# 19_SOLENOID_HB_1.net
KiCad netlist of a schematic drawn in Altium Designer
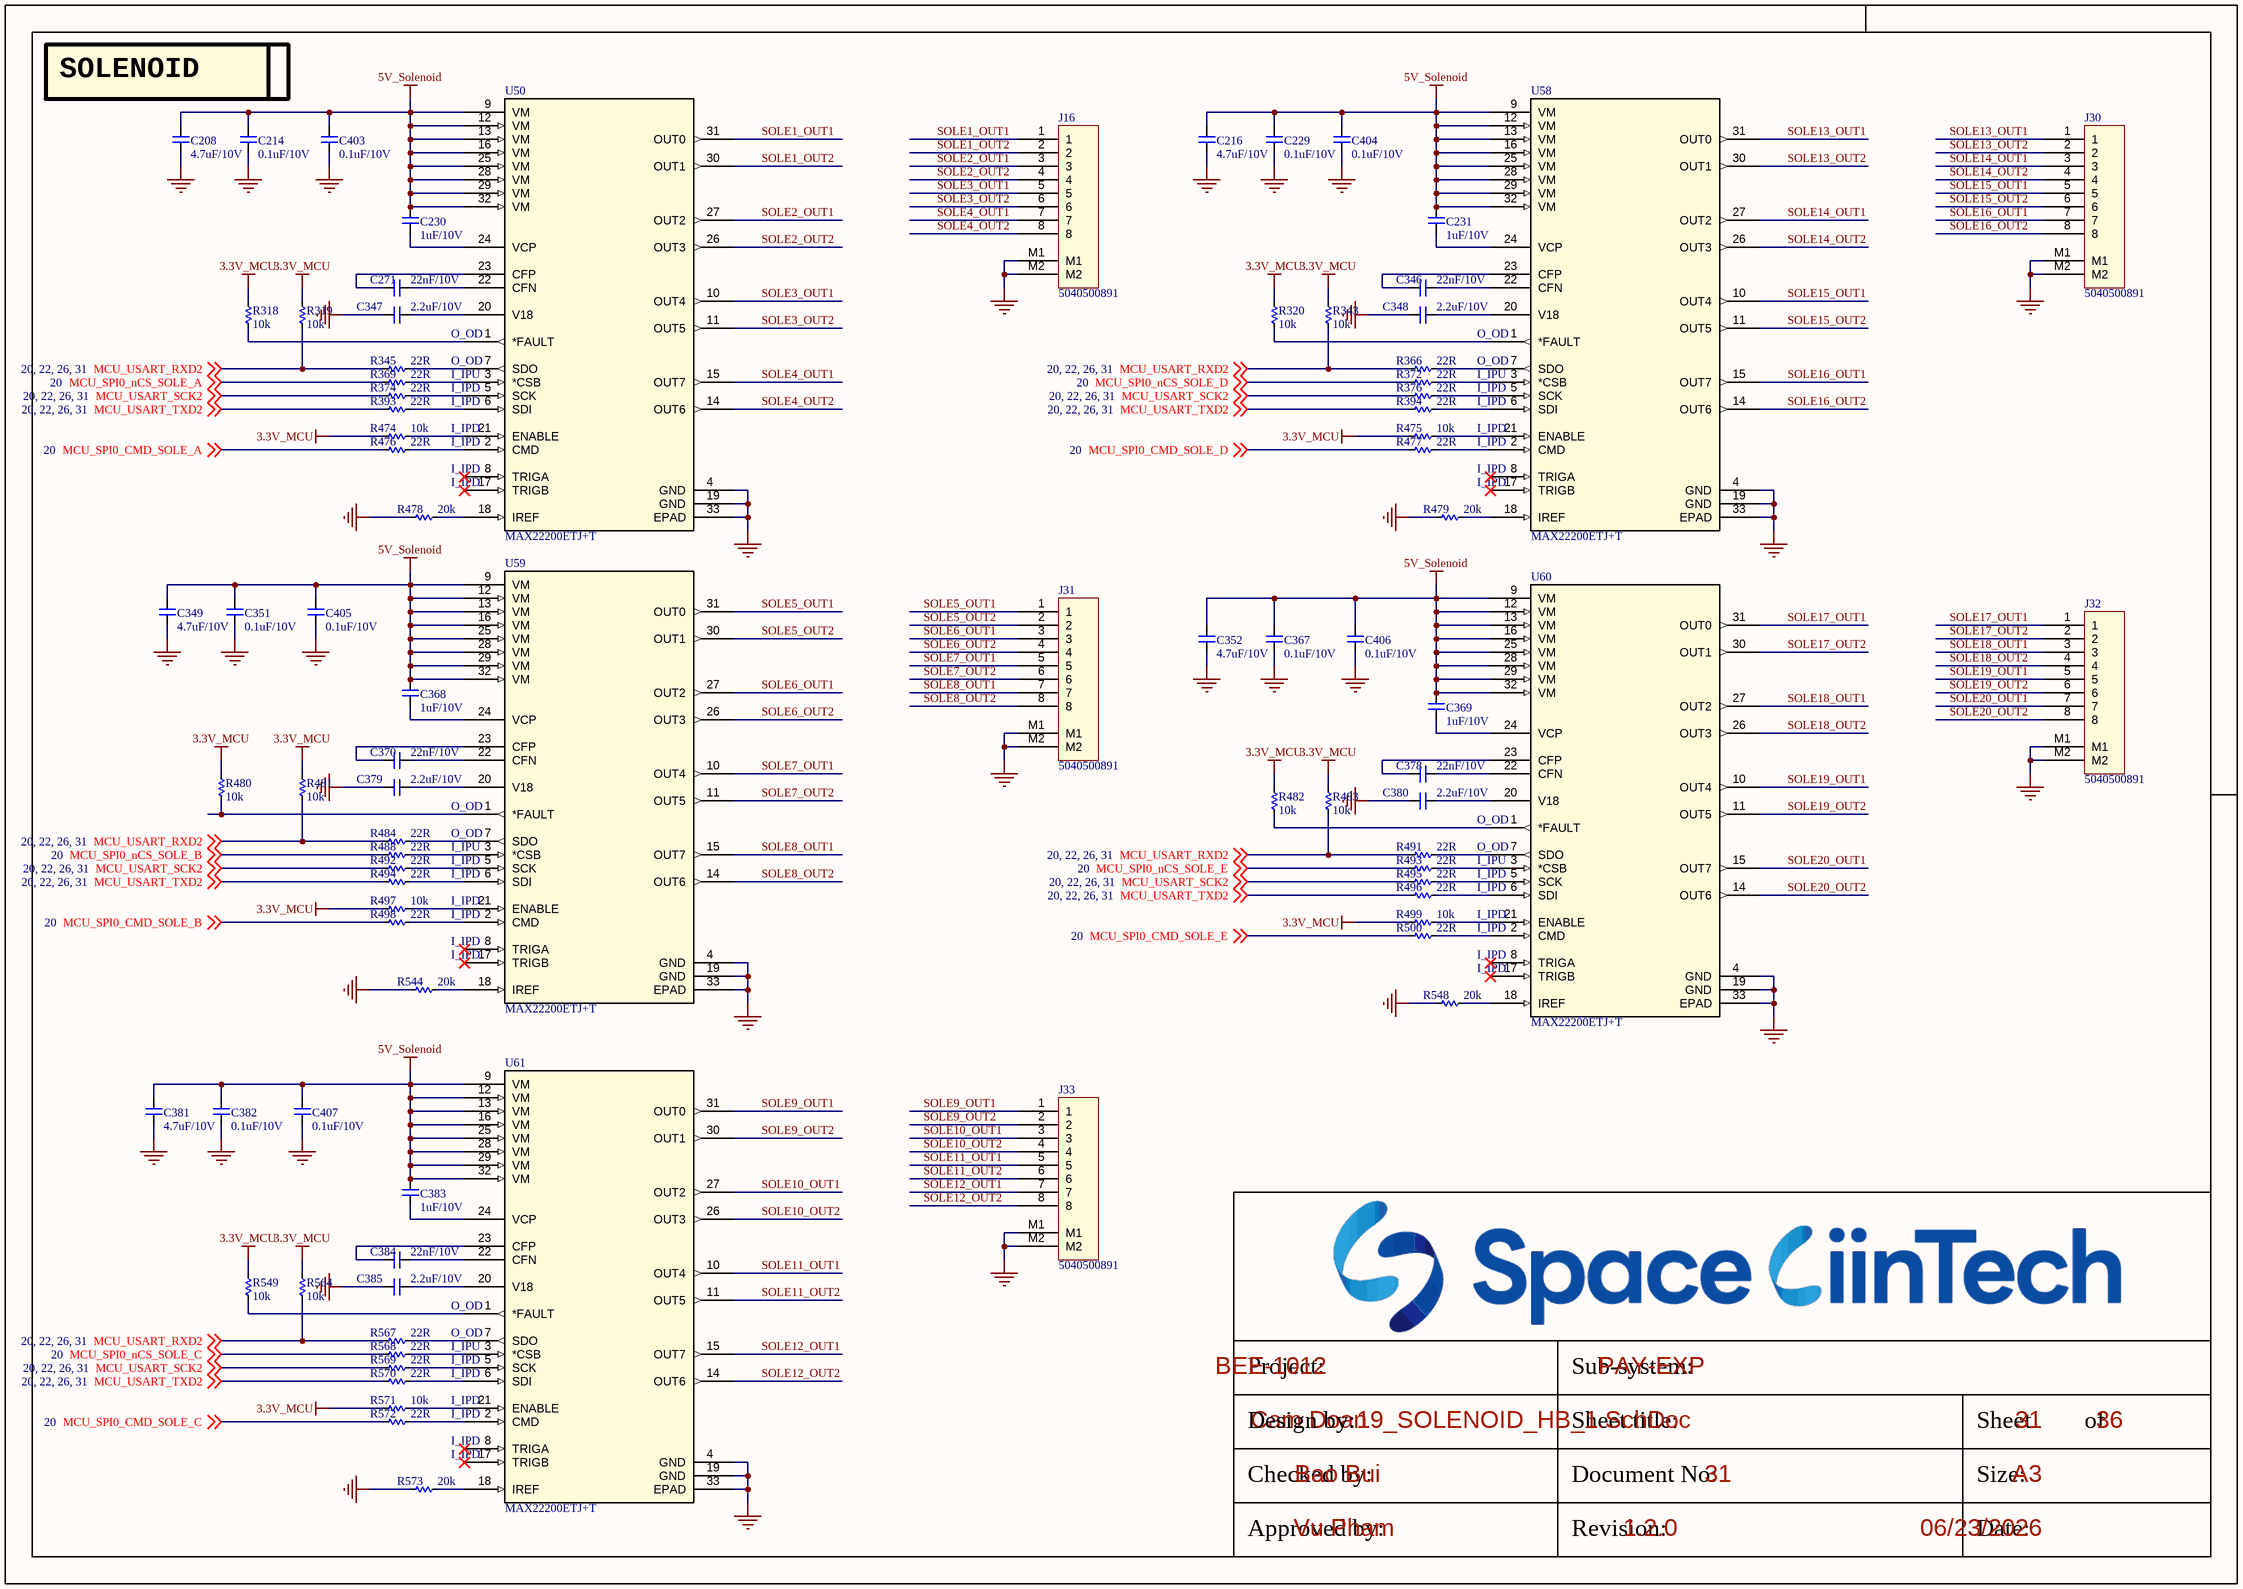
[diagram p0: 19_SOLENOID_HB_1.SchDoc]

(export (version "E")
  (design (tool "Eeschema 10.0.6"))
  (components
    (comp (ref "C208")
      (value "4.7uF/10V")
      (footprint "CAP_C_1005X60")
      (description "CAP CHIP")
      (libsource (lib "LABLIB") (part "_CAP_C_2"))
    )
    (comp (ref "C214")
      (value "0.1uF/10V")
      (footprint "CAP_C_1005X60")
      (description "CAP CHIP")
      (libsource (lib "LABLIB") (part "_CAP_C_2"))
    )
    (comp (ref "C216")
      (value "4.7uF/10V")
      (footprint "CAP_C_1005X60")
      (description "CAP CHIP")
      (libsource (lib "LABLIB") (part "_CAP_C_2"))
    )
    (comp (ref "C229")
      (value "0.1uF/10V")
      (footprint "CAP_C_1005X60")
      (description "CAP CHIP")
      (libsource (lib "LABLIB") (part "_CAP_C_2"))
    )
    (comp (ref "C230")
      (value "1uF/10V")
      (footprint "CAP_C_1005X60")
      (description "CAP CHIP")
      (libsource (lib "LABLIB") (part "_CAP_C_2"))
    )
    (comp (ref "C231")
      (value "1uF/10V")
      (footprint "CAP_C_1005X60")
      (description "CAP CHIP")
      (libsource (lib "LABLIB") (part "_CAP_C_2"))
    )
    (comp (ref "C271")
      (value "22nF/10V")
      (footprint "CAP_C_1005X60")
      (description "CAP CHIP")
      (libsource (lib "LABLIB") (part "_CAP_C_2"))
    )
    (comp (ref "C346")
      (value "22nF/10V")
      (footprint "CAP_C_1005X60")
      (description "CAP CHIP")
      (libsource (lib "LABLIB") (part "_CAP_C_2"))
    )
    (comp (ref "C347")
      (value "2.2uF/10V")
      (footprint "CAP_C_1005X60")
      (description "CAP CHIP")
      (libsource (lib "LABLIB") (part "_CAP_C_2"))
    )
    (comp (ref "C348")
      (value "2.2uF/10V")
      (footprint "CAP_C_1005X60")
      (description "CAP CHIP")
      (libsource (lib "LABLIB") (part "_CAP_C_2"))
    )
    (comp (ref "C349")
      (value "4.7uF/10V")
      (footprint "CAP_C_1005X60")
      (description "CAP CHIP")
      (libsource (lib "LABLIB") (part "_CAP_C_2"))
    )
    (comp (ref "C351")
      (value "0.1uF/10V")
      (footprint "CAP_C_1005X60")
      (description "CAP CHIP")
      (libsource (lib "LABLIB") (part "_CAP_C_2"))
    )
    (comp (ref "C352")
      (value "4.7uF/10V")
      (footprint "CAP_C_1005X60")
      (description "CAP CHIP")
      (libsource (lib "LABLIB") (part "_CAP_C_2"))
    )
    (comp (ref "C367")
      (value "0.1uF/10V")
      (footprint "CAP_C_1005X60")
      (description "CAP CHIP")
      (libsource (lib "LABLIB") (part "_CAP_C_2"))
    )
    (comp (ref "C368")
      (value "1uF/10V")
      (footprint "CAP_C_1005X60")
      (description "CAP CHIP")
      (libsource (lib "LABLIB") (part "_CAP_C_2"))
    )
    (comp (ref "C369")
      (value "1uF/10V")
      (footprint "CAP_C_1005X60")
      (description "CAP CHIP")
      (libsource (lib "LABLIB") (part "_CAP_C_2"))
    )
    (comp (ref "C370")
      (value "22nF/10V")
      (footprint "CAP_C_1005X60")
      (description "CAP CHIP")
      (libsource (lib "LABLIB") (part "_CAP_C_2"))
    )
    (comp (ref "C378")
      (value "22nF/10V")
      (footprint "CAP_C_1005X60")
      (description "CAP CHIP")
      (libsource (lib "LABLIB") (part "_CAP_C_2"))
    )
    (comp (ref "C379")
      (value "2.2uF/10V")
      (footprint "CAP_C_1005X60")
      (description "CAP CHIP")
      (libsource (lib "LABLIB") (part "_CAP_C_2"))
    )
    (comp (ref "C380")
      (value "2.2uF/10V")
      (footprint "CAP_C_1005X60")
      (description "CAP CHIP")
      (libsource (lib "LABLIB") (part "_CAP_C_2"))
    )
    (comp (ref "C381")
      (value "4.7uF/10V")
      (footprint "CAP_C_1005X60")
      (description "CAP CHIP")
      (libsource (lib "LABLIB") (part "_CAP_C_2"))
    )
    (comp (ref "C382")
      (value "0.1uF/10V")
      (footprint "CAP_C_1005X60")
      (description "CAP CHIP")
      (libsource (lib "LABLIB") (part "_CAP_C_2"))
    )
    (comp (ref "C383")
      (value "1uF/10V")
      (footprint "CAP_C_1005X60")
      (description "CAP CHIP")
      (libsource (lib "LABLIB") (part "_CAP_C_2"))
    )
    (comp (ref "C384")
      (value "22nF/10V")
      (footprint "CAP_C_1005X60")
      (description "CAP CHIP")
      (libsource (lib "LABLIB") (part "_CAP_C_2"))
    )
    (comp (ref "C385")
      (value "2.2uF/10V")
      (footprint "CAP_C_1005X60")
      (description "CAP CHIP")
      (libsource (lib "LABLIB") (part "_CAP_C_2"))
    )
    (comp (ref "C403")
      (value "0.1uF/10V")
      (footprint "CAP_C_1005X60")
      (description "CAP CHIP")
      (libsource (lib "LABLIB") (part "_CAP_C_2"))
    )
    (comp (ref "C404")
      (value "0.1uF/10V")
      (footprint "CAP_C_1005X60")
      (description "CAP CHIP")
      (libsource (lib "LABLIB") (part "_CAP_C_2"))
    )
    (comp (ref "C405")
      (value "0.1uF/10V")
      (footprint "CAP_C_1005X60")
      (description "CAP CHIP")
      (libsource (lib "LABLIB") (part "_CAP_C_2"))
    )
    (comp (ref "C406")
      (value "0.1uF/10V")
      (footprint "CAP_C_1005X60")
      (description "CAP CHIP")
      (libsource (lib "LABLIB") (part "_CAP_C_2"))
    )
    (comp (ref "C407")
      (value "0.1uF/10V")
      (footprint "CAP_C_1005X60")
      (description "CAP CHIP")
      (libsource (lib "LABLIB") (part "_CAP_C_2"))
    )
    (comp (ref "J16")
      (value "5040500891")
      (footprint "MOLEX_5040500891")
      (libsource (lib "LABLIB") (part "Header 8x1_2M"))
    )
    (comp (ref "J30")
      (value "5040500891")
      (footprint "MOLEX_5040500891")
      (libsource (lib "LABLIB") (part "Header 8x1_2M"))
    )
    (comp (ref "J31")
      (value "5040500891")
      (footprint "MOLEX_5040500891")
      (libsource (lib "LABLIB") (part "Header 8x1_2M"))
    )
    (comp (ref "J32")
      (value "5040500891")
      (footprint "MOLEX_5040500891")
      (libsource (lib "LABLIB") (part "Header 8x1_2M"))
    )
    (comp (ref "J33")
      (value "5040500891")
      (footprint "MOLEX_5040500891")
      (libsource (lib "LABLIB") (part "Header 8x1_2M"))
    )
    (comp (ref "R318")
      (value "10k")
      (footprint "RES_C_1005X40")
      (description "RES")
      (libsource (lib "LABLIB") (part "_RES_B_2"))
    )
    (comp (ref "R319")
      (value "10k")
      (footprint "RES_C_1005X40")
      (description "RES")
      (libsource (lib "LABLIB") (part "_RES_B_2"))
    )
    (comp (ref "R320")
      (value "10k")
      (footprint "RES_C_1005X40")
      (description "RES")
      (libsource (lib "LABLIB") (part "_RES_B_2"))
    )
    (comp (ref "R343")
      (value "10k")
      (footprint "RES_C_1005X40")
      (description "RES")
      (libsource (lib "LABLIB") (part "_RES_B_2"))
    )
    (comp (ref "R345")
      (value "22R")
      (footprint "RES_C_1005X40")
      (description "RES")
      (libsource (lib "LABLIB") (part "_RES_B_2"))
    )
    (comp (ref "R366")
      (value "22R")
      (footprint "RES_C_1005X40")
      (description "RES")
      (libsource (lib "LABLIB") (part "_RES_B_2"))
    )
    (comp (ref "R369")
      (value "22R")
      (footprint "RES_C_1005X40")
      (description "RES")
      (libsource (lib "LABLIB") (part "_RES_B_2"))
    )
    (comp (ref "R372")
      (value "22R")
      (footprint "RES_C_1005X40")
      (description "RES")
      (libsource (lib "LABLIB") (part "_RES_B_2"))
    )
    (comp (ref "R374")
      (value "22R")
      (footprint "RES_C_1005X40")
      (description "RES")
      (libsource (lib "LABLIB") (part "_RES_B_2"))
    )
    (comp (ref "R376")
      (value "22R")
      (footprint "RES_C_1005X40")
      (description "RES")
      (libsource (lib "LABLIB") (part "_RES_B_2"))
    )
    (comp (ref "R393")
      (value "22R")
      (footprint "RES_C_1005X40")
      (description "RES")
      (libsource (lib "LABLIB") (part "_RES_B_2"))
    )
    (comp (ref "R394")
      (value "22R")
      (footprint "RES_C_1005X40")
      (description "RES")
      (libsource (lib "LABLIB") (part "_RES_B_2"))
    )
    (comp (ref "R474")
      (value "10k")
      (footprint "RES_C_1005X40")
      (description "RES")
      (libsource (lib "LABLIB") (part "_RES_B_2"))
    )
    (comp (ref "R475")
      (value "10k")
      (footprint "RES_C_1005X40")
      (description "RES")
      (libsource (lib "LABLIB") (part "_RES_B_2"))
    )
    (comp (ref "R476")
      (value "22R")
      (footprint "RES_C_1005X40")
      (description "RES")
      (libsource (lib "LABLIB") (part "_RES_B_2"))
    )
    (comp (ref "R477")
      (value "22R")
      (footprint "RES_C_1005X40")
      (description "RES")
      (libsource (lib "LABLIB") (part "_RES_B_2"))
    )
    (comp (ref "R478")
      (value "20k")
      (footprint "RES_C_1005X40")
      (description "RES")
      (libsource (lib "LABLIB") (part "_RES_B_2"))
    )
    (comp (ref "R479")
      (value "20k")
      (footprint "RES_C_1005X40")
      (description "RES")
      (libsource (lib "LABLIB") (part "_RES_B_2"))
    )
    (comp (ref "R480")
      (value "10k")
      (footprint "RES_C_1005X40")
      (description "RES")
      (libsource (lib "LABLIB") (part "_RES_B_2"))
    )
    (comp (ref "R481")
      (value "10k")
      (footprint "RES_C_1005X40")
      (description "RES")
      (libsource (lib "LABLIB") (part "_RES_B_2"))
    )
    (comp (ref "R482")
      (value "10k")
      (footprint "RES_C_1005X40")
      (description "RES")
      (libsource (lib "LABLIB") (part "_RES_B_2"))
    )
    (comp (ref "R483")
      (value "10k")
      (footprint "RES_C_1005X40")
      (description "RES")
      (libsource (lib "LABLIB") (part "_RES_B_2"))
    )
    (comp (ref "R484")
      (value "22R")
      (footprint "RES_C_1005X40")
      (description "RES")
      (libsource (lib "LABLIB") (part "_RES_B_2"))
    )
    (comp (ref "R488")
      (value "22R")
      (footprint "RES_C_1005X40")
      (description "RES")
      (libsource (lib "LABLIB") (part "_RES_B_2"))
    )
    (comp (ref "R491")
      (value "22R")
      (footprint "RES_C_1005X40")
      (description "RES")
      (libsource (lib "LABLIB") (part "_RES_B_2"))
    )
    (comp (ref "R492")
      (value "22R")
      (footprint "RES_C_1005X40")
      (description "RES")
      (libsource (lib "LABLIB") (part "_RES_B_2"))
    )
    (comp (ref "R493")
      (value "22R")
      (footprint "RES_C_1005X40")
      (description "RES")
      (libsource (lib "LABLIB") (part "_RES_B_2"))
    )
    (comp (ref "R494")
      (value "22R")
      (footprint "RES_C_1005X40")
      (description "RES")
      (libsource (lib "LABLIB") (part "_RES_B_2"))
    )
    (comp (ref "R495")
      (value "22R")
      (footprint "RES_C_1005X40")
      (description "RES")
      (libsource (lib "LABLIB") (part "_RES_B_2"))
    )
    (comp (ref "R496")
      (value "22R")
      (footprint "RES_C_1005X40")
      (description "RES")
      (libsource (lib "LABLIB") (part "_RES_B_2"))
    )
    (comp (ref "R497")
      (value "10k")
      (footprint "RES_C_1005X40")
      (description "RES")
      (libsource (lib "LABLIB") (part "_RES_B_2"))
    )
    (comp (ref "R498")
      (value "22R")
      (footprint "RES_C_1005X40")
      (description "RES")
      (libsource (lib "LABLIB") (part "_RES_B_2"))
    )
    (comp (ref "R499")
      (value "10k")
      (footprint "RES_C_1005X40")
      (description "RES")
      (libsource (lib "LABLIB") (part "_RES_B_2"))
    )
    (comp (ref "R500")
      (value "22R")
      (footprint "RES_C_1005X40")
      (description "RES")
      (libsource (lib "LABLIB") (part "_RES_B_2"))
    )
    (comp (ref "R544")
      (value "20k")
      (footprint "RES_C_1005X40")
      (description "RES")
      (libsource (lib "LABLIB") (part "_RES_B_2"))
    )
    (comp (ref "R548")
      (value "20k")
      (footprint "RES_C_1005X40")
      (description "RES")
      (libsource (lib "LABLIB") (part "_RES_B_2"))
    )
    (comp (ref "R549")
      (value "10k")
      (footprint "RES_C_1005X40")
      (description "RES")
      (libsource (lib "LABLIB") (part "_RES_B_2"))
    )
    (comp (ref "R564")
      (value "10k")
      (footprint "RES_C_1005X40")
      (description "RES")
      (libsource (lib "LABLIB") (part "_RES_B_2"))
    )
    (comp (ref "R567")
      (value "22R")
      (footprint "RES_C_1005X40")
      (description "RES")
      (libsource (lib "LABLIB") (part "_RES_B_2"))
    )
    (comp (ref "R568")
      (value "22R")
      (footprint "RES_C_1005X40")
      (description "RES")
      (libsource (lib "LABLIB") (part "_RES_B_2"))
    )
    (comp (ref "R569")
      (value "22R")
      (footprint "RES_C_1005X40")
      (description "RES")
      (libsource (lib "LABLIB") (part "_RES_B_2"))
    )
    (comp (ref "R570")
      (value "22R")
      (footprint "RES_C_1005X40")
      (description "RES")
      (libsource (lib "LABLIB") (part "_RES_B_2"))
    )
    (comp (ref "R571")
      (value "10k")
      (footprint "RES_C_1005X40")
      (description "RES")
      (libsource (lib "LABLIB") (part "_RES_B_2"))
    )
    (comp (ref "R572")
      (value "22R")
      (footprint "RES_C_1005X40")
      (description "RES")
      (libsource (lib "LABLIB") (part "_RES_B_2"))
    )
    (comp (ref "R573")
      (value "20k")
      (footprint "RES_C_1005X40")
      (description "RES")
      (libsource (lib "LABLIB") (part "_RES_B_2"))
    )
    (comp (ref "U50")
      (value "MAX22200ETJ+T")
      (footprint "21-0140AK_T3255_8C_MXM")
      (description "36V, 1A Octal Integrated Serial-Controlled Solenoid and Motor Driver")
      (fields (field (name "COPYRIGHT") "Copyright (C) 2026 Ultra Librarian. All rights reserved."))
      (libsource (lib "LABLIB") (part "MAX22200ETJ+T"))
    )
    (comp (ref "U58")
      (value "MAX22200ETJ+T")
      (footprint "21-0140AK_T3255_8C_MXM")
      (description "36V, 1A Octal Integrated Serial-Controlled Solenoid and Motor Driver")
      (fields (field (name "COPYRIGHT") "Copyright (C) 2026 Ultra Librarian. All rights reserved."))
      (libsource (lib "LABLIB") (part "MAX22200ETJ+T"))
    )
    (comp (ref "U59")
      (value "MAX22200ETJ+T")
      (footprint "21-0140AK_T3255_8C_MXM")
      (description "36V, 1A Octal Integrated Serial-Controlled Solenoid and Motor Driver")
      (fields (field (name "COPYRIGHT") "Copyright (C) 2026 Ultra Librarian. All rights reserved."))
      (libsource (lib "LABLIB") (part "MAX22200ETJ+T"))
    )
    (comp (ref "U60")
      (value "MAX22200ETJ+T")
      (footprint "21-0140AK_T3255_8C_MXM")
      (description "36V, 1A Octal Integrated Serial-Controlled Solenoid and Motor Driver")
      (fields (field (name "COPYRIGHT") "Copyright (C) 2026 Ultra Librarian. All rights reserved."))
      (libsource (lib "LABLIB") (part "MAX22200ETJ+T"))
    )
    (comp (ref "U61")
      (value "MAX22200ETJ+T")
      (footprint "21-0140AK_T3255_8C_MXM")
      (description "36V, 1A Octal Integrated Serial-Controlled Solenoid and Motor Driver")
      (fields (field (name "COPYRIGHT") "Copyright (C) 2026 Ultra Librarian. All rights reserved."))
      (libsource (lib "LABLIB") (part "MAX22200ETJ+T"))
    )
  )
  (nets
    (net (code "1") (name "/SOLE1_OUT1") (class "Default")
      (node (ref "J16") (pin "1") (pinfunction "1_1") (pintype "passive"))
      (node (ref "U50") (pin "31") (pinfunction "OUT0_31") (pintype "output"))
    )
    (net (code "2") (name "/SOLE1_OUT2") (class "Default")
      (node (ref "J16") (pin "2") (pinfunction "2_2") (pintype "passive"))
      (node (ref "U50") (pin "30") (pinfunction "OUT1_30") (pintype "output"))
    )
    (net (code "3") (name "/SOLE2_OUT1") (class "Default")
      (node (ref "J16") (pin "3") (pinfunction "3_3") (pintype "passive"))
      (node (ref "U50") (pin "27") (pinfunction "OUT2_27") (pintype "output"))
    )
    (net (code "4") (name "/SOLE2_OUT2") (class "Default")
      (node (ref "J16") (pin "4") (pinfunction "4_4") (pintype "passive"))
      (node (ref "U50") (pin "26") (pinfunction "OUT3_26") (pintype "output"))
    )
    (net (code "5") (name "/SOLE3_OUT1") (class "Default")
      (node (ref "J16") (pin "5") (pinfunction "5_5") (pintype "passive"))
      (node (ref "U50") (pin "10") (pinfunction "OUT4_10") (pintype "output"))
    )
    (net (code "6") (name "/SOLE3_OUT2") (class "Default")
      (node (ref "J16") (pin "6") (pinfunction "6_6") (pintype "passive"))
      (node (ref "U50") (pin "11") (pinfunction "OUT5_11") (pintype "output"))
    )
    (net (code "7") (name "/SOLE4_OUT1") (class "Default")
      (node (ref "J16") (pin "7") (pinfunction "7_7") (pintype "passive"))
      (node (ref "U50") (pin "15") (pinfunction "OUT7_15") (pintype "output"))
    )
    (net (code "8") (name "/SOLE4_OUT2") (class "Default")
      (node (ref "J16") (pin "8") (pinfunction "8_8") (pintype "passive"))
      (node (ref "U50") (pin "14") (pinfunction "OUT6_14") (pintype "output"))
    )
    (net (code "9") (name "/SOLE5_OUT1") (class "Default")
      (node (ref "J31") (pin "1") (pinfunction "1_1") (pintype "passive"))
      (node (ref "U59") (pin "31") (pinfunction "OUT0_31") (pintype "output"))
    )
    (net (code "10") (name "/SOLE5_OUT2") (class "Default")
      (node (ref "J31") (pin "2") (pinfunction "2_2") (pintype "passive"))
      (node (ref "U59") (pin "30") (pinfunction "OUT1_30") (pintype "output"))
    )
    (net (code "11") (name "/SOLE6_OUT1") (class "Default")
      (node (ref "J31") (pin "3") (pinfunction "3_3") (pintype "passive"))
      (node (ref "U59") (pin "27") (pinfunction "OUT2_27") (pintype "output"))
    )
    (net (code "12") (name "/SOLE6_OUT2") (class "Default")
      (node (ref "J31") (pin "4") (pinfunction "4_4") (pintype "passive"))
      (node (ref "U59") (pin "26") (pinfunction "OUT3_26") (pintype "output"))
    )
    (net (code "13") (name "/SOLE7_OUT1") (class "Default")
      (node (ref "J31") (pin "5") (pinfunction "5_5") (pintype "passive"))
      (node (ref "U59") (pin "10") (pinfunction "OUT4_10") (pintype "output"))
    )
    (net (code "14") (name "/SOLE7_OUT2") (class "Default")
      (node (ref "J31") (pin "6") (pinfunction "6_6") (pintype "passive"))
      (node (ref "U59") (pin "11") (pinfunction "OUT5_11") (pintype "output"))
    )
    (net (code "15") (name "/SOLE8_OUT1") (class "Default")
      (node (ref "J31") (pin "7") (pinfunction "7_7") (pintype "passive"))
      (node (ref "U59") (pin "15") (pinfunction "OUT7_15") (pintype "output"))
    )
    (net (code "16") (name "/SOLE8_OUT2") (class "Default")
      (node (ref "J31") (pin "8") (pinfunction "8_8") (pintype "passive"))
      (node (ref "U59") (pin "14") (pinfunction "OUT6_14") (pintype "output"))
    )
    (net (code "17") (name "/SOLE9_OUT1") (class "Default")
      (node (ref "J33") (pin "1") (pinfunction "1_1") (pintype "passive"))
      (node (ref "U61") (pin "31") (pinfunction "OUT0_31") (pintype "output"))
    )
    (net (code "18") (name "/SOLE9_OUT2") (class "Default")
      (node (ref "J33") (pin "2") (pinfunction "2_2") (pintype "passive"))
      (node (ref "U61") (pin "30") (pinfunction "OUT1_30") (pintype "output"))
    )
    (net (code "19") (name "/SOLE10_OUT1") (class "Default")
      (node (ref "J33") (pin "3") (pinfunction "3_3") (pintype "passive"))
      (node (ref "U61") (pin "27") (pinfunction "OUT2_27") (pintype "output"))
    )
    (net (code "20") (name "/SOLE10_OUT2") (class "Default")
      (node (ref "J33") (pin "4") (pinfunction "4_4") (pintype "passive"))
      (node (ref "U61") (pin "26") (pinfunction "OUT3_26") (pintype "output"))
    )
    (net (code "21") (name "/SOLE11_OUT1") (class "Default")
      (node (ref "J33") (pin "5") (pinfunction "5_5") (pintype "passive"))
      (node (ref "U61") (pin "10") (pinfunction "OUT4_10") (pintype "output"))
    )
    (net (code "22") (name "/SOLE11_OUT2") (class "Default")
      (node (ref "J33") (pin "6") (pinfunction "6_6") (pintype "passive"))
      (node (ref "U61") (pin "11") (pinfunction "OUT5_11") (pintype "output"))
    )
    (net (code "23") (name "/SOLE12_OUT1") (class "Default")
      (node (ref "J33") (pin "7") (pinfunction "7_7") (pintype "passive"))
      (node (ref "U61") (pin "15") (pinfunction "OUT7_15") (pintype "output"))
    )
    (net (code "24") (name "/SOLE12_OUT2") (class "Default")
      (node (ref "J33") (pin "8") (pinfunction "8_8") (pintype "passive"))
      (node (ref "U61") (pin "14") (pinfunction "OUT6_14") (pintype "output"))
    )
    (net (code "25") (name "/SOLE13_OUT1") (class "Default")
      (node (ref "J30") (pin "1") (pinfunction "1_1") (pintype "passive"))
      (node (ref "U58") (pin "31") (pinfunction "OUT0_31") (pintype "output"))
    )
    (net (code "26") (name "/SOLE13_OUT2") (class "Default")
      (node (ref "J30") (pin "2") (pinfunction "2_2") (pintype "passive"))
      (node (ref "U58") (pin "30") (pinfunction "OUT1_30") (pintype "output"))
    )
    (net (code "27") (name "/SOLE14_OUT1") (class "Default")
      (node (ref "J30") (pin "3") (pinfunction "3_3") (pintype "passive"))
      (node (ref "U58") (pin "27") (pinfunction "OUT2_27") (pintype "output"))
    )
    (net (code "28") (name "/SOLE14_OUT2") (class "Default")
      (node (ref "J30") (pin "4") (pinfunction "4_4") (pintype "passive"))
      (node (ref "U58") (pin "26") (pinfunction "OUT3_26") (pintype "output"))
    )
    (net (code "29") (name "/SOLE15_OUT1") (class "Default")
      (node (ref "J30") (pin "5") (pinfunction "5_5") (pintype "passive"))
      (node (ref "U58") (pin "10") (pinfunction "OUT4_10") (pintype "output"))
    )
    (net (code "30") (name "/SOLE15_OUT2") (class "Default")
      (node (ref "J30") (pin "6") (pinfunction "6_6") (pintype "passive"))
      (node (ref "U58") (pin "11") (pinfunction "OUT5_11") (pintype "output"))
    )
    (net (code "31") (name "/SOLE16_OUT1") (class "Default")
      (node (ref "J30") (pin "7") (pinfunction "7_7") (pintype "passive"))
      (node (ref "U58") (pin "15") (pinfunction "OUT7_15") (pintype "output"))
    )
    (net (code "32") (name "/SOLE16_OUT2") (class "Default")
      (node (ref "J30") (pin "8") (pinfunction "8_8") (pintype "passive"))
      (node (ref "U58") (pin "14") (pinfunction "OUT6_14") (pintype "output"))
    )
    (net (code "33") (name "/SOLE17_OUT1") (class "Default")
      (node (ref "J32") (pin "1") (pinfunction "1_1") (pintype "passive"))
      (node (ref "U60") (pin "31") (pinfunction "OUT0_31") (pintype "output"))
    )
    (net (code "34") (name "/SOLE17_OUT2") (class "Default")
      (node (ref "J32") (pin "2") (pinfunction "2_2") (pintype "passive"))
      (node (ref "U60") (pin "30") (pinfunction "OUT1_30") (pintype "output"))
    )
    (net (code "35") (name "/SOLE18_OUT1") (class "Default")
      (node (ref "J32") (pin "3") (pinfunction "3_3") (pintype "passive"))
      (node (ref "U60") (pin "27") (pinfunction "OUT2_27") (pintype "output"))
    )
    (net (code "36") (name "/SOLE18_OUT2") (class "Default")
      (node (ref "J32") (pin "4") (pinfunction "4_4") (pintype "passive"))
      (node (ref "U60") (pin "26") (pinfunction "OUT3_26") (pintype "output"))
    )
    (net (code "37") (name "/SOLE19_OUT1") (class "Default")
      (node (ref "J32") (pin "5") (pinfunction "5_5") (pintype "passive"))
      (node (ref "U60") (pin "10") (pinfunction "OUT4_10") (pintype "output"))
    )
    (net (code "38") (name "/SOLE19_OUT2") (class "Default")
      (node (ref "J32") (pin "6") (pinfunction "6_6") (pintype "passive"))
      (node (ref "U60") (pin "11") (pinfunction "OUT5_11") (pintype "output"))
    )
    (net (code "39") (name "/SOLE20_OUT1") (class "Default")
      (node (ref "J32") (pin "7") (pinfunction "7_7") (pintype "passive"))
      (node (ref "U60") (pin "15") (pinfunction "OUT7_15") (pintype "output"))
    )
    (net (code "40") (name "/SOLE20_OUT2") (class "Default")
      (node (ref "J32") (pin "8") (pinfunction "8_8") (pintype "passive"))
      (node (ref "U60") (pin "14") (pinfunction "OUT6_14") (pintype "output"))
    )
    (net (code "41") (name "3.3V_MCU") (class "Default")
      (node (ref "R318") (pin "1") (pinfunction "1_1") (pintype "passive"))
      (node (ref "R319") (pin "1") (pinfunction "1_1") (pintype "passive"))
      (node (ref "R320") (pin "1") (pinfunction "1_1") (pintype "passive"))
      (node (ref "R343") (pin "1") (pinfunction "1_1") (pintype "passive"))
      (node (ref "R474") (pin "1") (pinfunction "1_1") (pintype "passive"))
      (node (ref "R475") (pin "1") (pinfunction "1_1") (pintype "passive"))
      (node (ref "R480") (pin "1") (pinfunction "1_1") (pintype "passive"))
      (node (ref "R481") (pin "1") (pinfunction "1_1") (pintype "passive"))
      (node (ref "R482") (pin "1") (pinfunction "1_1") (pintype "passive"))
      (node (ref "R483") (pin "1") (pinfunction "1_1") (pintype "passive"))
      (node (ref "R497") (pin "1") (pinfunction "1_1") (pintype "passive"))
      (node (ref "R499") (pin "1") (pinfunction "1_1") (pintype "passive"))
      (node (ref "R549") (pin "1") (pinfunction "1_1") (pintype "passive"))
      (node (ref "R564") (pin "1") (pinfunction "1_1") (pintype "passive"))
      (node (ref "R571") (pin "1") (pinfunction "1_1") (pintype "passive"))
    )
    (net (code "42") (name "5V_Solenoid") (class "Default")
      (node (ref "C208") (pin "2") (pinfunction "2_2") (pintype "passive"))
      (node (ref "C214") (pin "2") (pinfunction "2_2") (pintype "passive"))
      (node (ref "C216") (pin "2") (pinfunction "2_2") (pintype "passive"))
      (node (ref "C229") (pin "2") (pinfunction "2_2") (pintype "passive"))
      (node (ref "C230") (pin "2") (pinfunction "2_2") (pintype "passive"))
      (node (ref "C231") (pin "2") (pinfunction "2_2") (pintype "passive"))
      (node (ref "C349") (pin "2") (pinfunction "2_2") (pintype "passive"))
      (node (ref "C351") (pin "2") (pinfunction "2_2") (pintype "passive"))
      (node (ref "C352") (pin "2") (pinfunction "2_2") (pintype "passive"))
      (node (ref "C367") (pin "2") (pinfunction "2_2") (pintype "passive"))
      (node (ref "C368") (pin "2") (pinfunction "2_2") (pintype "passive"))
      (node (ref "C369") (pin "2") (pinfunction "2_2") (pintype "passive"))
      (node (ref "C381") (pin "2") (pinfunction "2_2") (pintype "passive"))
      (node (ref "C382") (pin "2") (pinfunction "2_2") (pintype "passive"))
      (node (ref "C383") (pin "2") (pinfunction "2_2") (pintype "passive"))
      (node (ref "C403") (pin "2") (pinfunction "2_2") (pintype "passive"))
      (node (ref "C404") (pin "2") (pinfunction "2_2") (pintype "passive"))
      (node (ref "C405") (pin "2") (pinfunction "2_2") (pintype "passive"))
      (node (ref "C406") (pin "2") (pinfunction "2_2") (pintype "passive"))
      (node (ref "C407") (pin "2") (pinfunction "2_2") (pintype "passive"))
      (node (ref "U50") (pin "12") (pinfunction "VM_12") (pintype "input"))
      (node (ref "U50") (pin "13") (pinfunction "VM_13") (pintype "input"))
      (node (ref "U50") (pin "16") (pinfunction "VM_16") (pintype "input"))
      (node (ref "U50") (pin "25") (pinfunction "VM_25") (pintype "input"))
      (node (ref "U50") (pin "28") (pinfunction "VM_28") (pintype "input"))
      (node (ref "U50") (pin "29") (pinfunction "VM_29") (pintype "input"))
      (node (ref "U50") (pin "32") (pinfunction "VM_32") (pintype "input"))
      (node (ref "U50") (pin "9") (pinfunction "VM_9") (pintype "power_in"))
      (node (ref "U58") (pin "12") (pinfunction "VM_12") (pintype "input"))
      (node (ref "U58") (pin "13") (pinfunction "VM_13") (pintype "input"))
      (node (ref "U58") (pin "16") (pinfunction "VM_16") (pintype "input"))
      (node (ref "U58") (pin "25") (pinfunction "VM_25") (pintype "input"))
      (node (ref "U58") (pin "28") (pinfunction "VM_28") (pintype "input"))
      (node (ref "U58") (pin "29") (pinfunction "VM_29") (pintype "input"))
      (node (ref "U58") (pin "32") (pinfunction "VM_32") (pintype "input"))
      (node (ref "U58") (pin "9") (pinfunction "VM_9") (pintype "power_in"))
      (node (ref "U59") (pin "12") (pinfunction "VM_12") (pintype "input"))
      (node (ref "U59") (pin "13") (pinfunction "VM_13") (pintype "input"))
      (node (ref "U59") (pin "16") (pinfunction "VM_16") (pintype "input"))
      (node (ref "U59") (pin "25") (pinfunction "VM_25") (pintype "input"))
      (node (ref "U59") (pin "28") (pinfunction "VM_28") (pintype "input"))
      (node (ref "U59") (pin "29") (pinfunction "VM_29") (pintype "input"))
      (node (ref "U59") (pin "32") (pinfunction "VM_32") (pintype "input"))
      (node (ref "U59") (pin "9") (pinfunction "VM_9") (pintype "power_in"))
      (node (ref "U60") (pin "12") (pinfunction "VM_12") (pintype "input"))
      (node (ref "U60") (pin "13") (pinfunction "VM_13") (pintype "input"))
      (node (ref "U60") (pin "16") (pinfunction "VM_16") (pintype "input"))
      (node (ref "U60") (pin "25") (pinfunction "VM_25") (pintype "input"))
      (node (ref "U60") (pin "28") (pinfunction "VM_28") (pintype "input"))
      (node (ref "U60") (pin "29") (pinfunction "VM_29") (pintype "input"))
      (node (ref "U60") (pin "32") (pinfunction "VM_32") (pintype "input"))
      (node (ref "U60") (pin "9") (pinfunction "VM_9") (pintype "power_in"))
      (node (ref "U61") (pin "12") (pinfunction "VM_12") (pintype "input"))
      (node (ref "U61") (pin "13") (pinfunction "VM_13") (pintype "input"))
      (node (ref "U61") (pin "16") (pinfunction "VM_16") (pintype "input"))
      (node (ref "U61") (pin "25") (pinfunction "VM_25") (pintype "input"))
      (node (ref "U61") (pin "28") (pinfunction "VM_28") (pintype "input"))
      (node (ref "U61") (pin "29") (pinfunction "VM_29") (pintype "input"))
      (node (ref "U61") (pin "32") (pinfunction "VM_32") (pintype "input"))
      (node (ref "U61") (pin "9") (pinfunction "VM_9") (pintype "power_in"))
    )
    (net (code "43") (name "GND") (class "Default")
      (node (ref "C208") (pin "1") (pinfunction "1_1") (pintype "passive"))
      (node (ref "C214") (pin "1") (pinfunction "1_1") (pintype "passive"))
      (node (ref "C216") (pin "1") (pinfunction "1_1") (pintype "passive"))
      (node (ref "C229") (pin "1") (pinfunction "1_1") (pintype "passive"))
      (node (ref "C347") (pin "1") (pinfunction "1_1") (pintype "passive"))
      (node (ref "C348") (pin "1") (pinfunction "1_1") (pintype "passive"))
      (node (ref "C349") (pin "1") (pinfunction "1_1") (pintype "passive"))
      (node (ref "C351") (pin "1") (pinfunction "1_1") (pintype "passive"))
      (node (ref "C352") (pin "1") (pinfunction "1_1") (pintype "passive"))
      (node (ref "C367") (pin "1") (pinfunction "1_1") (pintype "passive"))
      (node (ref "C379") (pin "1") (pinfunction "1_1") (pintype "passive"))
      (node (ref "C380") (pin "1") (pinfunction "1_1") (pintype "passive"))
      (node (ref "C381") (pin "1") (pinfunction "1_1") (pintype "passive"))
      (node (ref "C382") (pin "1") (pinfunction "1_1") (pintype "passive"))
      (node (ref "C385") (pin "1") (pinfunction "1_1") (pintype "passive"))
      (node (ref "C403") (pin "1") (pinfunction "1_1") (pintype "passive"))
      (node (ref "C404") (pin "1") (pinfunction "1_1") (pintype "passive"))
      (node (ref "C405") (pin "1") (pinfunction "1_1") (pintype "passive"))
      (node (ref "C406") (pin "1") (pinfunction "1_1") (pintype "passive"))
      (node (ref "C407") (pin "1") (pinfunction "1_1") (pintype "passive"))
      (node (ref "J16") (pin "M1") (pinfunction "M1_M1") (pintype "passive"))
      (node (ref "J16") (pin "M2") (pinfunction "M2_M2") (pintype "passive"))
      (node (ref "J30") (pin "M1") (pinfunction "M1_M1") (pintype "passive"))
      (node (ref "J30") (pin "M2") (pinfunction "M2_M2") (pintype "passive"))
      (node (ref "J31") (pin "M1") (pinfunction "M1_M1") (pintype "passive"))
      (node (ref "J31") (pin "M2") (pinfunction "M2_M2") (pintype "passive"))
      (node (ref "J32") (pin "M1") (pinfunction "M1_M1") (pintype "passive"))
      (node (ref "J32") (pin "M2") (pinfunction "M2_M2") (pintype "passive"))
      (node (ref "J33") (pin "M1") (pinfunction "M1_M1") (pintype "passive"))
      (node (ref "J33") (pin "M2") (pinfunction "M2_M2") (pintype "passive"))
      (node (ref "R478") (pin "1") (pinfunction "1_1") (pintype "passive"))
      (node (ref "R479") (pin "1") (pinfunction "1_1") (pintype "passive"))
      (node (ref "R544") (pin "1") (pinfunction "1_1") (pintype "passive"))
      (node (ref "R548") (pin "1") (pinfunction "1_1") (pintype "passive"))
      (node (ref "R573") (pin "1") (pinfunction "1_1") (pintype "passive"))
      (node (ref "U50") (pin "19") (pinfunction "GND_19") (pintype "power_in"))
      (node (ref "U50") (pin "33") (pinfunction "EPAD_33") (pintype "power_in"))
      (node (ref "U50") (pin "4") (pinfunction "GND_4") (pintype "power_in"))
      (node (ref "U58") (pin "19") (pinfunction "GND_19") (pintype "power_in"))
      (node (ref "U58") (pin "33") (pinfunction "EPAD_33") (pintype "power_in"))
      (node (ref "U58") (pin "4") (pinfunction "GND_4") (pintype "power_in"))
      (node (ref "U59") (pin "19") (pinfunction "GND_19") (pintype "power_in"))
      (node (ref "U59") (pin "33") (pinfunction "EPAD_33") (pintype "power_in"))
      (node (ref "U59") (pin "4") (pinfunction "GND_4") (pintype "power_in"))
      (node (ref "U60") (pin "19") (pinfunction "GND_19") (pintype "power_in"))
      (node (ref "U60") (pin "33") (pinfunction "EPAD_33") (pintype "power_in"))
      (node (ref "U60") (pin "4") (pinfunction "GND_4") (pintype "power_in"))
      (node (ref "U61") (pin "19") (pinfunction "GND_19") (pintype "power_in"))
      (node (ref "U61") (pin "33") (pinfunction "EPAD_33") (pintype "power_in"))
      (node (ref "U61") (pin "4") (pinfunction "GND_4") (pintype "power_in"))
    )
    (net (code "44") (name "MCU_SPI0_CMD_SOLE_A") (class "Default")
      (node (ref "R476") (pin "1") (pinfunction "1_1") (pintype "passive"))
    )
    (net (code "45") (name "MCU_SPI0_CMD_SOLE_B") (class "Default")
      (node (ref "R498") (pin "1") (pinfunction "1_1") (pintype "passive"))
    )
    (net (code "46") (name "MCU_SPI0_CMD_SOLE_C") (class "Default")
      (node (ref "R572") (pin "1") (pinfunction "1_1") (pintype "passive"))
    )
    (net (code "47") (name "MCU_SPI0_CMD_SOLE_D") (class "Default")
      (node (ref "R477") (pin "1") (pinfunction "1_1") (pintype "passive"))
    )
    (net (code "48") (name "MCU_SPI0_CMD_SOLE_E") (class "Default")
      (node (ref "R500") (pin "1") (pinfunction "1_1") (pintype "passive"))
    )
    (net (code "49") (name "MCU_SPI0_nCS_SOLE_A") (class "Default")
      (node (ref "R369") (pin "1") (pinfunction "1_1") (pintype "passive"))
    )
    (net (code "50") (name "MCU_SPI0_nCS_SOLE_B") (class "Default")
      (node (ref "R488") (pin "1") (pinfunction "1_1") (pintype "passive"))
    )
    (net (code "51") (name "MCU_SPI0_nCS_SOLE_C") (class "Default")
      (node (ref "R568") (pin "1") (pinfunction "1_1") (pintype "passive"))
    )
    (net (code "52") (name "MCU_SPI0_nCS_SOLE_D") (class "Default")
      (node (ref "R372") (pin "1") (pinfunction "1_1") (pintype "passive"))
    )
    (net (code "53") (name "MCU_SPI0_nCS_SOLE_E") (class "Default")
      (node (ref "R493") (pin "1") (pinfunction "1_1") (pintype "passive"))
    )
    (net (code "54") (name "MCU_USART_RXD2") (class "Default")
      (node (ref "R319") (pin "2") (pinfunction "2_2") (pintype "passive"))
      (node (ref "R343") (pin "2") (pinfunction "2_2") (pintype "passive"))
      (node (ref "R345") (pin "1") (pinfunction "1_1") (pintype "passive"))
      (node (ref "R366") (pin "1") (pinfunction "1_1") (pintype "passive"))
      (node (ref "R481") (pin "2") (pinfunction "2_2") (pintype "passive"))
      (node (ref "R483") (pin "2") (pinfunction "2_2") (pintype "passive"))
      (node (ref "R484") (pin "1") (pinfunction "1_1") (pintype "passive"))
      (node (ref "R491") (pin "1") (pinfunction "1_1") (pintype "passive"))
      (node (ref "R564") (pin "2") (pinfunction "2_2") (pintype "passive"))
      (node (ref "R567") (pin "1") (pinfunction "1_1") (pintype "passive"))
    )
    (net (code "55") (name "MCU_USART_SCK2") (class "Default")
      (node (ref "R374") (pin "1") (pinfunction "1_1") (pintype "passive"))
      (node (ref "R376") (pin "1") (pinfunction "1_1") (pintype "passive"))
      (node (ref "R492") (pin "1") (pinfunction "1_1") (pintype "passive"))
      (node (ref "R495") (pin "1") (pinfunction "1_1") (pintype "passive"))
      (node (ref "R569") (pin "1") (pinfunction "1_1") (pintype "passive"))
    )
    (net (code "56") (name "MCU_USART_TXD2") (class "Default")
      (node (ref "R393") (pin "1") (pinfunction "1_1") (pintype "passive"))
      (node (ref "R394") (pin "1") (pinfunction "1_1") (pintype "passive"))
      (node (ref "R494") (pin "1") (pinfunction "1_1") (pintype "passive"))
      (node (ref "R496") (pin "1") (pinfunction "1_1") (pintype "passive"))
      (node (ref "R570") (pin "1") (pinfunction "1_1") (pintype "passive"))
    )
    (net (code "57") (name "Net-(U50-*CSB)") (class "Default")
      (node (ref "R369") (pin "2") (pinfunction "2_2") (pintype "passive"))
      (node (ref "U50") (pin "3") (pinfunction "*CSB_3") (pintype "input"))
    )
    (net (code "58") (name "Net-(U50-*FAULT)") (class "Default")
      (node (ref "R318") (pin "2") (pinfunction "2_2") (pintype "passive"))
      (node (ref "U50") (pin "1") (pinfunction "*FAULT_1") (pintype "output"))
    )
    (net (code "59") (name "Net-(U50-CFN)") (class "Default")
      (node (ref "C271") (pin "1") (pinfunction "1_1") (pintype "passive"))
      (node (ref "U50") (pin "22") (pinfunction "CFN_22") (pintype "power_in"))
    )
    (net (code "60") (name "Net-(U50-CFP)") (class "Default")
      (node (ref "C271") (pin "2") (pinfunction "2_2") (pintype "passive"))
      (node (ref "U50") (pin "23") (pinfunction "CFP_23") (pintype "power_in"))
    )
    (net (code "61") (name "Net-(U50-CMD)") (class "Default")
      (node (ref "R476") (pin "2") (pinfunction "2_2") (pintype "passive"))
      (node (ref "U50") (pin "2") (pinfunction "CMD_2") (pintype "input"))
    )
    (net (code "62") (name "Net-(U50-ENABLE)") (class "Default")
      (node (ref "R474") (pin "2") (pinfunction "2_2") (pintype "passive"))
      (node (ref "U50") (pin "21") (pinfunction "ENABLE_21") (pintype "input"))
    )
    (net (code "63") (name "Net-(U50-IREF)") (class "Default")
      (node (ref "R478") (pin "2") (pinfunction "2_2") (pintype "passive"))
      (node (ref "U50") (pin "18") (pinfunction "IREF_18") (pintype "input"))
    )
    (net (code "64") (name "Net-(U50-SCK)") (class "Default")
      (node (ref "R374") (pin "2") (pinfunction "2_2") (pintype "passive"))
      (node (ref "U50") (pin "5") (pinfunction "SCK_5") (pintype "input"))
    )
    (net (code "65") (name "Net-(U50-SDI)") (class "Default")
      (node (ref "R393") (pin "2") (pinfunction "2_2") (pintype "passive"))
      (node (ref "U50") (pin "6") (pinfunction "SDI_6") (pintype "input"))
    )
    (net (code "66") (name "Net-(U50-SDO)") (class "Default")
      (node (ref "R345") (pin "2") (pinfunction "2_2") (pintype "passive"))
      (node (ref "U50") (pin "7") (pinfunction "SDO_7") (pintype "output"))
    )
    (net (code "67") (name "Net-(U50-V18)") (class "Default")
      (node (ref "C347") (pin "2") (pinfunction "2_2") (pintype "passive"))
      (node (ref "U50") (pin "20") (pinfunction "V18_20") (pintype "power_in"))
    )
    (net (code "68") (name "Net-(U50-VCP)") (class "Default")
      (node (ref "C230") (pin "1") (pinfunction "1_1") (pintype "passive"))
      (node (ref "U50") (pin "24") (pinfunction "VCP_24") (pintype "power_in"))
    )
    (net (code "69") (name "Net-(U58-*CSB)") (class "Default")
      (node (ref "R372") (pin "2") (pinfunction "2_2") (pintype "passive"))
      (node (ref "U58") (pin "3") (pinfunction "*CSB_3") (pintype "input"))
    )
    (net (code "70") (name "Net-(U58-*FAULT)") (class "Default")
      (node (ref "R320") (pin "2") (pinfunction "2_2") (pintype "passive"))
      (node (ref "U58") (pin "1") (pinfunction "*FAULT_1") (pintype "output"))
    )
    (net (code "71") (name "Net-(U58-CFN)") (class "Default")
      (node (ref "C346") (pin "1") (pinfunction "1_1") (pintype "passive"))
      (node (ref "U58") (pin "22") (pinfunction "CFN_22") (pintype "power_in"))
    )
    (net (code "72") (name "Net-(U58-CFP)") (class "Default")
      (node (ref "C346") (pin "2") (pinfunction "2_2") (pintype "passive"))
      (node (ref "U58") (pin "23") (pinfunction "CFP_23") (pintype "power_in"))
    )
    (net (code "73") (name "Net-(U58-CMD)") (class "Default")
      (node (ref "R477") (pin "2") (pinfunction "2_2") (pintype "passive"))
      (node (ref "U58") (pin "2") (pinfunction "CMD_2") (pintype "input"))
    )
    (net (code "74") (name "Net-(U58-ENABLE)") (class "Default")
      (node (ref "R475") (pin "2") (pinfunction "2_2") (pintype "passive"))
      (node (ref "U58") (pin "21") (pinfunction "ENABLE_21") (pintype "input"))
    )
    (net (code "75") (name "Net-(U58-IREF)") (class "Default")
      (node (ref "R479") (pin "2") (pinfunction "2_2") (pintype "passive"))
      (node (ref "U58") (pin "18") (pinfunction "IREF_18") (pintype "input"))
    )
    (net (code "76") (name "Net-(U58-SCK)") (class "Default")
      (node (ref "R376") (pin "2") (pinfunction "2_2") (pintype "passive"))
      (node (ref "U58") (pin "5") (pinfunction "SCK_5") (pintype "input"))
    )
    (net (code "77") (name "Net-(U58-SDI)") (class "Default")
      (node (ref "R394") (pin "2") (pinfunction "2_2") (pintype "passive"))
      (node (ref "U58") (pin "6") (pinfunction "SDI_6") (pintype "input"))
    )
    (net (code "78") (name "Net-(U58-SDO)") (class "Default")
      (node (ref "R366") (pin "2") (pinfunction "2_2") (pintype "passive"))
      (node (ref "U58") (pin "7") (pinfunction "SDO_7") (pintype "output"))
    )
    (net (code "79") (name "Net-(U58-V18)") (class "Default")
      (node (ref "C348") (pin "2") (pinfunction "2_2") (pintype "passive"))
      (node (ref "U58") (pin "20") (pinfunction "V18_20") (pintype "power_in"))
    )
    (net (code "80") (name "Net-(U58-VCP)") (class "Default")
      (node (ref "C231") (pin "1") (pinfunction "1_1") (pintype "passive"))
      (node (ref "U58") (pin "24") (pinfunction "VCP_24") (pintype "power_in"))
    )
    (net (code "81") (name "Net-(U59-*CSB)") (class "Default")
      (node (ref "R488") (pin "2") (pinfunction "2_2") (pintype "passive"))
      (node (ref "U59") (pin "3") (pinfunction "*CSB_3") (pintype "input"))
    )
    (net (code "82") (name "Net-(U59-*FAULT)") (class "Default")
      (node (ref "R480") (pin "2") (pinfunction "2_2") (pintype "passive"))
      (node (ref "U59") (pin "1") (pinfunction "*FAULT_1") (pintype "output"))
    )
    (net (code "83") (name "Net-(U59-CFN)") (class "Default")
      (node (ref "C370") (pin "1") (pinfunction "1_1") (pintype "passive"))
      (node (ref "U59") (pin "22") (pinfunction "CFN_22") (pintype "power_in"))
    )
    (net (code "84") (name "Net-(U59-CFP)") (class "Default")
      (node (ref "C370") (pin "2") (pinfunction "2_2") (pintype "passive"))
      (node (ref "U59") (pin "23") (pinfunction "CFP_23") (pintype "power_in"))
    )
    (net (code "85") (name "Net-(U59-CMD)") (class "Default")
      (node (ref "R498") (pin "2") (pinfunction "2_2") (pintype "passive"))
      (node (ref "U59") (pin "2") (pinfunction "CMD_2") (pintype "input"))
    )
    (net (code "86") (name "Net-(U59-ENABLE)") (class "Default")
      (node (ref "R497") (pin "2") (pinfunction "2_2") (pintype "passive"))
      (node (ref "U59") (pin "21") (pinfunction "ENABLE_21") (pintype "input"))
    )
    (net (code "87") (name "Net-(U59-IREF)") (class "Default")
      (node (ref "R544") (pin "2") (pinfunction "2_2") (pintype "passive"))
      (node (ref "U59") (pin "18") (pinfunction "IREF_18") (pintype "input"))
    )
    (net (code "88") (name "Net-(U59-SCK)") (class "Default")
      (node (ref "R492") (pin "2") (pinfunction "2_2") (pintype "passive"))
      (node (ref "U59") (pin "5") (pinfunction "SCK_5") (pintype "input"))
    )
    (net (code "89") (name "Net-(U59-SDI)") (class "Default")
      (node (ref "R494") (pin "2") (pinfunction "2_2") (pintype "passive"))
      (node (ref "U59") (pin "6") (pinfunction "SDI_6") (pintype "input"))
    )
    (net (code "90") (name "Net-(U59-SDO)") (class "Default")
      (node (ref "R484") (pin "2") (pinfunction "2_2") (pintype "passive"))
      (node (ref "U59") (pin "7") (pinfunction "SDO_7") (pintype "output"))
    )
    (net (code "91") (name "Net-(U59-V18)") (class "Default")
      (node (ref "C379") (pin "2") (pinfunction "2_2") (pintype "passive"))
      (node (ref "U59") (pin "20") (pinfunction "V18_20") (pintype "power_in"))
    )
    (net (code "92") (name "Net-(U59-VCP)") (class "Default")
      (node (ref "C368") (pin "1") (pinfunction "1_1") (pintype "passive"))
      (node (ref "U59") (pin "24") (pinfunction "VCP_24") (pintype "power_in"))
    )
    (net (code "93") (name "Net-(U60-*CSB)") (class "Default")
      (node (ref "R493") (pin "2") (pinfunction "2_2") (pintype "passive"))
      (node (ref "U60") (pin "3") (pinfunction "*CSB_3") (pintype "input"))
    )
    (net (code "94") (name "Net-(U60-*FAULT)") (class "Default")
      (node (ref "R482") (pin "2") (pinfunction "2_2") (pintype "passive"))
      (node (ref "U60") (pin "1") (pinfunction "*FAULT_1") (pintype "output"))
    )
    (net (code "95") (name "Net-(U60-CFN)") (class "Default")
      (node (ref "C378") (pin "1") (pinfunction "1_1") (pintype "passive"))
      (node (ref "U60") (pin "22") (pinfunction "CFN_22") (pintype "power_in"))
    )
    (net (code "96") (name "Net-(U60-CFP)") (class "Default")
      (node (ref "C378") (pin "2") (pinfunction "2_2") (pintype "passive"))
      (node (ref "U60") (pin "23") (pinfunction "CFP_23") (pintype "power_in"))
    )
    (net (code "97") (name "Net-(U60-CMD)") (class "Default")
      (node (ref "R500") (pin "2") (pinfunction "2_2") (pintype "passive"))
      (node (ref "U60") (pin "2") (pinfunction "CMD_2") (pintype "input"))
    )
    (net (code "98") (name "Net-(U60-ENABLE)") (class "Default")
      (node (ref "R499") (pin "2") (pinfunction "2_2") (pintype "passive"))
      (node (ref "U60") (pin "21") (pinfunction "ENABLE_21") (pintype "input"))
    )
    (net (code "99") (name "Net-(U60-IREF)") (class "Default")
      (node (ref "R548") (pin "2") (pinfunction "2_2") (pintype "passive"))
      (node (ref "U60") (pin "18") (pinfunction "IREF_18") (pintype "input"))
    )
    (net (code "100") (name "Net-(U60-SCK)") (class "Default")
      (node (ref "R495") (pin "2") (pinfunction "2_2") (pintype "passive"))
      (node (ref "U60") (pin "5") (pinfunction "SCK_5") (pintype "input"))
    )
    (net (code "101") (name "Net-(U60-SDI)") (class "Default")
      (node (ref "R496") (pin "2") (pinfunction "2_2") (pintype "passive"))
      (node (ref "U60") (pin "6") (pinfunction "SDI_6") (pintype "input"))
    )
    (net (code "102") (name "Net-(U60-SDO)") (class "Default")
      (node (ref "R491") (pin "2") (pinfunction "2_2") (pintype "passive"))
      (node (ref "U60") (pin "7") (pinfunction "SDO_7") (pintype "output"))
    )
    (net (code "103") (name "Net-(U60-V18)") (class "Default")
      (node (ref "C380") (pin "2") (pinfunction "2_2") (pintype "passive"))
      (node (ref "U60") (pin "20") (pinfunction "V18_20") (pintype "power_in"))
    )
    (net (code "104") (name "Net-(U60-VCP)") (class "Default")
      (node (ref "C369") (pin "1") (pinfunction "1_1") (pintype "passive"))
      (node (ref "U60") (pin "24") (pinfunction "VCP_24") (pintype "power_in"))
    )
    (net (code "105") (name "Net-(U61-*CSB)") (class "Default")
      (node (ref "R568") (pin "2") (pinfunction "2_2") (pintype "passive"))
      (node (ref "U61") (pin "3") (pinfunction "*CSB_3") (pintype "input"))
    )
    (net (code "106") (name "Net-(U61-*FAULT)") (class "Default")
      (node (ref "R549") (pin "2") (pinfunction "2_2") (pintype "passive"))
      (node (ref "U61") (pin "1") (pinfunction "*FAULT_1") (pintype "output"))
    )
    (net (code "107") (name "Net-(U61-CFN)") (class "Default")
      (node (ref "C384") (pin "1") (pinfunction "1_1") (pintype "passive"))
      (node (ref "U61") (pin "22") (pinfunction "CFN_22") (pintype "power_in"))
    )
    (net (code "108") (name "Net-(U61-CFP)") (class "Default")
      (node (ref "C384") (pin "2") (pinfunction "2_2") (pintype "passive"))
      (node (ref "U61") (pin "23") (pinfunction "CFP_23") (pintype "power_in"))
    )
    (net (code "109") (name "Net-(U61-CMD)") (class "Default")
      (node (ref "R572") (pin "2") (pinfunction "2_2") (pintype "passive"))
      (node (ref "U61") (pin "2") (pinfunction "CMD_2") (pintype "input"))
    )
    (net (code "110") (name "Net-(U61-ENABLE)") (class "Default")
      (node (ref "R571") (pin "2") (pinfunction "2_2") (pintype "passive"))
      (node (ref "U61") (pin "21") (pinfunction "ENABLE_21") (pintype "input"))
    )
    (net (code "111") (name "Net-(U61-IREF)") (class "Default")
      (node (ref "R573") (pin "2") (pinfunction "2_2") (pintype "passive"))
      (node (ref "U61") (pin "18") (pinfunction "IREF_18") (pintype "input"))
    )
    (net (code "112") (name "Net-(U61-SCK)") (class "Default")
      (node (ref "R569") (pin "2") (pinfunction "2_2") (pintype "passive"))
      (node (ref "U61") (pin "5") (pinfunction "SCK_5") (pintype "input"))
    )
    (net (code "113") (name "Net-(U61-SDI)") (class "Default")
      (node (ref "R570") (pin "2") (pinfunction "2_2") (pintype "passive"))
      (node (ref "U61") (pin "6") (pinfunction "SDI_6") (pintype "input"))
    )
    (net (code "114") (name "Net-(U61-SDO)") (class "Default")
      (node (ref "R567") (pin "2") (pinfunction "2_2") (pintype "passive"))
      (node (ref "U61") (pin "7") (pinfunction "SDO_7") (pintype "output"))
    )
    (net (code "115") (name "Net-(U61-V18)") (class "Default")
      (node (ref "C385") (pin "2") (pinfunction "2_2") (pintype "passive"))
      (node (ref "U61") (pin "20") (pinfunction "V18_20") (pintype "power_in"))
    )
    (net (code "116") (name "Net-(U61-VCP)") (class "Default")
      (node (ref "C383") (pin "1") (pinfunction "1_1") (pintype "passive"))
      (node (ref "U61") (pin "24") (pinfunction "VCP_24") (pintype "power_in"))
    )
    (net (code "117") (name "unconnected-(U50-TRIGA-Pad8)") (class "Default")
      (node (ref "U50") (pin "8") (pinfunction "TRIGA_8") (pintype "input+no_connect"))
    )
    (net (code "118") (name "unconnected-(U50-TRIGB-Pad17)") (class "Default")
      (node (ref "U50") (pin "17") (pinfunction "TRIGB_17") (pintype "input+no_connect"))
    )
    (net (code "119") (name "unconnected-(U58-TRIGA-Pad8)") (class "Default")
      (node (ref "U58") (pin "8") (pinfunction "TRIGA_8") (pintype "input+no_connect"))
    )
    (net (code "120") (name "unconnected-(U58-TRIGB-Pad17)") (class "Default")
      (node (ref "U58") (pin "17") (pinfunction "TRIGB_17") (pintype "input+no_connect"))
    )
    (net (code "121") (name "unconnected-(U59-TRIGA-Pad8)") (class "Default")
      (node (ref "U59") (pin "8") (pinfunction "TRIGA_8") (pintype "input+no_connect"))
    )
    (net (code "122") (name "unconnected-(U59-TRIGB-Pad17)") (class "Default")
      (node (ref "U59") (pin "17") (pinfunction "TRIGB_17") (pintype "input+no_connect"))
    )
    (net (code "123") (name "unconnected-(U60-TRIGA-Pad8)") (class "Default")
      (node (ref "U60") (pin "8") (pinfunction "TRIGA_8") (pintype "input+no_connect"))
    )
    (net (code "124") (name "unconnected-(U60-TRIGB-Pad17)") (class "Default")
      (node (ref "U60") (pin "17") (pinfunction "TRIGB_17") (pintype "input+no_connect"))
    )
    (net (code "125") (name "unconnected-(U61-TRIGA-Pad8)") (class "Default")
      (node (ref "U61") (pin "8") (pinfunction "TRIGA_8") (pintype "input+no_connect"))
    )
    (net (code "126") (name "unconnected-(U61-TRIGB-Pad17)") (class "Default")
      (node (ref "U61") (pin "17") (pinfunction "TRIGB_17") (pintype "input+no_connect"))
    )
  )
)
